# Sheet1.net
KiCad netlist of a schematic drawn in Altium Designer
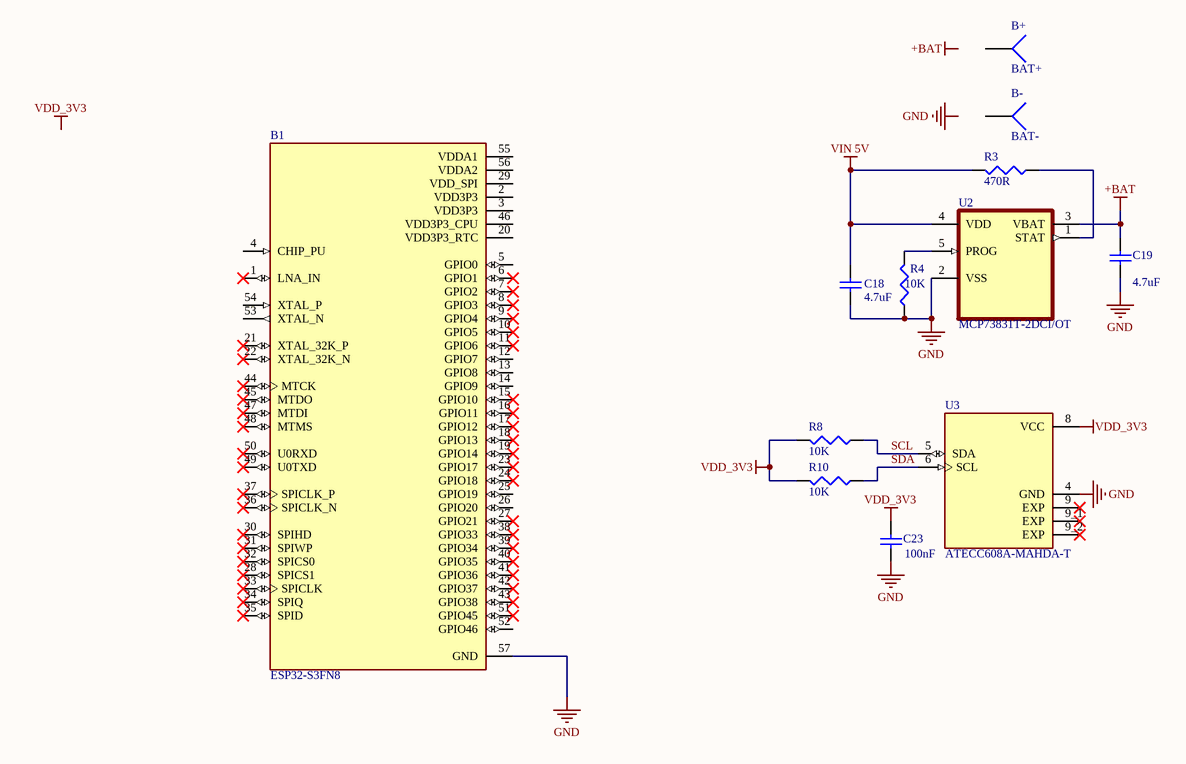
[diagram p0: Sheet1.SchDoc]

(export (version "E")
  (design (tool "Eeschema 10.0.6"))
  (components
    (comp (ref "B+")
      (value "BAT+")
      (footprint "PIN1")
      (description "Socket")
      (fields (field (name "PUBLISHER") "Altium Limited"))
      (libsource (lib "Miscellaneous Connectors") (part "Socket"))
    )
    (comp (ref "B-")
      (value "BAT-")
      (footprint "PIN1")
      (description "Socket")
      (fields (field (name "PUBLISHER") "Altium Limited"))
      (libsource (lib "Miscellaneous Connectors") (part "Socket"))
    )
    (comp (ref "B1")
      (value "ESP32-S3FN8")
      (footprint "ESP32-S3FN8:QFN40P700X700X90-57N")
      (fields (field (name "MF") "{'manufacturer': u'Espressif Systems'}"))
      (libsource (lib "*") (part "ESP32-S3FN8"))
    )
    (comp (ref "C18")
      (value "4.7uF")
      (footprint "C1206")
      (description "Capacitor (Semiconductor SIM Model)")
      (fields (field (name "Comment") "Cap Semi") (field (name "PUBLISHER") "Altium Limited"))
      (libsource (lib "Miscellaneous Devices") (part "Cap Semi"))
    )
    (comp (ref "C19")
      (value "4.7uF")
      (footprint "C1206")
      (description "Capacitor (Semiconductor SIM Model)")
      (fields (field (name "Comment") "Cap Semi") (field (name "PUBLISHER") "Altium Limited"))
      (libsource (lib "Miscellaneous Devices") (part "Cap Semi"))
    )
    (comp (ref "C23")
      (value "100nF")
      (footprint "C1206")
      (description "Capacitor (Semiconductor SIM Model)")
      (fields (field (name "Comment") "Cap Semi") (field (name "PUBLISHER") "Altium Limited"))
      (libsource (lib "Miscellaneous Devices") (part "Cap Semi"))
    )
    (comp (ref "R3")
      (value "470R")
      (footprint "J1-0603")
      (description "Resistor")
      (fields (field (name "Comment") "Res3") (field (name "PUBLISHER") "Altium Limited"))
      (libsource (lib "Miscellaneous Devices") (part "Res3"))
    )
    (comp (ref "R4")
      (value "10K")
      (footprint "J1-0603")
      (description "Resistor")
      (fields (field (name "Comment") "Res3") (field (name "PUBLISHER") "Altium Limited"))
      (libsource (lib "Miscellaneous Devices") (part "Res3"))
    )
    (comp (ref "R8")
      (value "10K")
      (footprint "J1-0603")
      (description "Resistor")
      (fields (field (name "Comment") "Res3") (field (name "PUBLISHER") "Altium Limited"))
      (libsource (lib "Miscellaneous Devices") (part "Res3"))
    )
    (comp (ref "R10")
      (value "10K")
      (footprint "J1-0603")
      (description "Resistor")
      (fields (field (name "Comment") "Res3") (field (name "PUBLISHER") "Altium Limited"))
      (libsource (lib "Miscellaneous Devices") (part "Res3"))
    )
    (comp (ref "U2")
      (value "MCP73831T-2DCI/OT")
      (footprint "MCP73831T-2DCI_OT:SOT95P270X145-5N")
      (description "Li-Polymer Charge Management Controllers, SOT23-5")
      (fields (field (name "MF") "{'manufacturer': u'Microchip'}") (field (name "MP") "MCP73831T-2DCI-OT"))
      (libsource (lib "*") (part "MCP73831T-2DCI/OT"))
    )
    (comp (ref "U3")
      (value "ATECC608A-MAHDA-T")
      (footprint "ATECC608A-MAHDA-T:SON50P200X300X60-9N")
      (description "IC AUTHENTICATION CHIP 8UDFN")
      (fields (field (name "MF") "{'manufacturer': u'Microchip Technology'}"))
      (libsource (lib "*") (part "ATECC608A-MAHDA-T"))
    )
  )
  (nets
    (net (code "1") (name "+BAT") (class "Default")
      (node (ref "C19") (pin "2") (pinfunction "2_2") (pintype "passive"))
      (node (ref "U2") (pin "3") (pinfunction "VBAT_3") (pintype "power_in"))
    )
    (net (code "2") (name "/SCL") (class "Default")
      (node (ref "R8") (pin "1") (pinfunction "1_1") (pintype "passive"))
      (node (ref "U3") (pin "5") (pinfunction "SDA_5") (pintype "bidirectional"))
    )
    (net (code "3") (name "/SDA") (class "Default")
      (node (ref "R10") (pin "1") (pinfunction "1_1") (pintype "passive"))
      (node (ref "U3") (pin "6") (pinfunction "SCL_6") (pintype "input"))
    )
    (net (code "4") (name "GND") (class "Default")
      (node (ref "B1") (pin "57") (pinfunction "GND_57") (pintype "power_in"))
      (node (ref "C18") (pin "1") (pinfunction "1_1") (pintype "passive"))
      (node (ref "C19") (pin "1") (pinfunction "1_1") (pintype "passive"))
      (node (ref "C23") (pin "1") (pinfunction "1_1") (pintype "passive"))
      (node (ref "R4") (pin "1") (pinfunction "1_1") (pintype "passive"))
      (node (ref "U2") (pin "2") (pinfunction "VSS_2") (pintype "power_in"))
      (node (ref "U3") (pin "4") (pinfunction "GND_4") (pintype "power_in"))
    )
    (net (code "5") (name "Net-(U2-PROG)") (class "Default")
      (node (ref "R4") (pin "2") (pinfunction "2_2") (pintype "passive"))
      (node (ref "U2") (pin "5") (pinfunction "PROG_5") (pintype "input"))
    )
    (net (code "6") (name "Net-(U2-STAT)") (class "Default")
      (node (ref "R3") (pin "1") (pinfunction "1_1") (pintype "passive"))
      (node (ref "U2") (pin "1") (pinfunction "STAT_1") (pintype "output"))
    )
    (net (code "7") (name "VDD_3V3") (class "Default")
      (node (ref "C23") (pin "2") (pinfunction "2_2") (pintype "passive"))
      (node (ref "R10") (pin "2") (pinfunction "2_2") (pintype "passive"))
      (node (ref "R8") (pin "2") (pinfunction "2_2") (pintype "passive"))
      (node (ref "U3") (pin "8") (pinfunction "VCC_8") (pintype "power_in"))
    )
    (net (code "8") (name "VIN 5V") (class "Default")
      (node (ref "C18") (pin "2") (pinfunction "2_2") (pintype "passive"))
      (node (ref "R3") (pin "2") (pinfunction "2_2") (pintype "passive"))
      (node (ref "U2") (pin "4") (pinfunction "VDD_4") (pintype "power_in"))
    )
    (net (code "9") (name "unconnected-(B+-Pad1)") (class "Default")
      (node (ref "B+") (pin "1") (pinfunction "1_1") (pintype "passive"))
    )
    (net (code "10") (name "unconnected-(B--Pad1)") (class "Default")
      (node (ref "B-") (pin "1") (pinfunction "1_1") (pintype "passive"))
    )
    (net (code "11") (name "unconnected-(B1-CHIP_PU-Pad4)") (class "Default")
      (node (ref "B1") (pin "4") (pinfunction "CHIP_PU_4") (pintype "input"))
    )
    (net (code "12") (name "unconnected-(B1-GPIO0-Pad5)") (class "Default")
      (node (ref "B1") (pin "5") (pinfunction "GPIO0_5") (pintype "bidirectional"))
    )
    (net (code "13") (name "unconnected-(B1-GPIO1-Pad6)") (class "Default")
      (node (ref "B1") (pin "6") (pinfunction "GPIO1_6") (pintype "bidirectional+no_connect"))
    )
    (net (code "14") (name "unconnected-(B1-GPIO2-Pad7)") (class "Default")
      (node (ref "B1") (pin "7") (pinfunction "GPIO2_7") (pintype "bidirectional+no_connect"))
    )
    (net (code "15") (name "unconnected-(B1-GPIO3-Pad8)") (class "Default")
      (node (ref "B1") (pin "8") (pinfunction "GPIO3_8") (pintype "bidirectional+no_connect"))
    )
    (net (code "16") (name "unconnected-(B1-GPIO4-Pad9)") (class "Default")
      (node (ref "B1") (pin "9") (pinfunction "GPIO4_9") (pintype "bidirectional+no_connect"))
    )
    (net (code "17") (name "unconnected-(B1-GPIO5-Pad10)") (class "Default")
      (node (ref "B1") (pin "10") (pinfunction "GPIO5_10") (pintype "bidirectional+no_connect"))
    )
    (net (code "18") (name "unconnected-(B1-GPIO6-Pad11)") (class "Default")
      (node (ref "B1") (pin "11") (pinfunction "GPIO6_11") (pintype "bidirectional+no_connect"))
    )
    (net (code "19") (name "unconnected-(B1-GPIO7-Pad12)") (class "Default")
      (node (ref "B1") (pin "12") (pinfunction "GPIO7_12") (pintype "bidirectional"))
    )
    (net (code "20") (name "unconnected-(B1-GPIO8-Pad13)") (class "Default")
      (node (ref "B1") (pin "13") (pinfunction "GPIO8_13") (pintype "bidirectional"))
    )
    (net (code "21") (name "unconnected-(B1-GPIO9-Pad14)") (class "Default")
      (node (ref "B1") (pin "14") (pinfunction "GPIO9_14") (pintype "bidirectional"))
    )
    (net (code "22") (name "unconnected-(B1-GPIO10-Pad15)") (class "Default")
      (node (ref "B1") (pin "15") (pinfunction "GPIO10_15") (pintype "bidirectional+no_connect"))
    )
    (net (code "23") (name "unconnected-(B1-GPIO11-Pad16)") (class "Default")
      (node (ref "B1") (pin "16") (pinfunction "GPIO11_16") (pintype "bidirectional+no_connect"))
    )
    (net (code "24") (name "unconnected-(B1-GPIO12-Pad17)") (class "Default")
      (node (ref "B1") (pin "17") (pinfunction "GPIO12_17") (pintype "bidirectional+no_connect"))
    )
    (net (code "25") (name "unconnected-(B1-GPIO13-Pad18)") (class "Default")
      (node (ref "B1") (pin "18") (pinfunction "GPIO13_18") (pintype "bidirectional+no_connect"))
    )
    (net (code "26") (name "unconnected-(B1-GPIO14-Pad19)") (class "Default")
      (node (ref "B1") (pin "19") (pinfunction "GPIO14_19") (pintype "bidirectional+no_connect"))
    )
    (net (code "27") (name "unconnected-(B1-GPIO17-Pad23)") (class "Default")
      (node (ref "B1") (pin "23") (pinfunction "GPIO17_23") (pintype "bidirectional+no_connect"))
    )
    (net (code "28") (name "unconnected-(B1-GPIO18-Pad24)") (class "Default")
      (node (ref "B1") (pin "24") (pinfunction "GPIO18_24") (pintype "bidirectional+no_connect"))
    )
    (net (code "29") (name "unconnected-(B1-GPIO19-Pad25)") (class "Default")
      (node (ref "B1") (pin "25") (pinfunction "GPIO19_25") (pintype "bidirectional"))
    )
    (net (code "30") (name "unconnected-(B1-GPIO20-Pad26)") (class "Default")
      (node (ref "B1") (pin "26") (pinfunction "GPIO20_26") (pintype "bidirectional"))
    )
    (net (code "31") (name "unconnected-(B1-GPIO21-Pad27)") (class "Default")
      (node (ref "B1") (pin "27") (pinfunction "GPIO21_27") (pintype "bidirectional+no_connect"))
    )
    (net (code "32") (name "unconnected-(B1-GPIO33-Pad38)") (class "Default")
      (node (ref "B1") (pin "38") (pinfunction "GPIO33_38") (pintype "bidirectional+no_connect"))
    )
    (net (code "33") (name "unconnected-(B1-GPIO34-Pad39)") (class "Default")
      (node (ref "B1") (pin "39") (pinfunction "GPIO34_39") (pintype "bidirectional+no_connect"))
    )
    (net (code "34") (name "unconnected-(B1-GPIO35-Pad40)") (class "Default")
      (node (ref "B1") (pin "40") (pinfunction "GPIO35_40") (pintype "bidirectional+no_connect"))
    )
    (net (code "35") (name "unconnected-(B1-GPIO36-Pad41)") (class "Default")
      (node (ref "B1") (pin "41") (pinfunction "GPIO36_41") (pintype "bidirectional+no_connect"))
    )
    (net (code "36") (name "unconnected-(B1-GPIO37-Pad42)") (class "Default")
      (node (ref "B1") (pin "42") (pinfunction "GPIO37_42") (pintype "bidirectional+no_connect"))
    )
    (net (code "37") (name "unconnected-(B1-GPIO38-Pad43)") (class "Default")
      (node (ref "B1") (pin "43") (pinfunction "GPIO38_43") (pintype "bidirectional+no_connect"))
    )
    (net (code "38") (name "unconnected-(B1-GPIO45-Pad51)") (class "Default")
      (node (ref "B1") (pin "51") (pinfunction "GPIO45_51") (pintype "bidirectional+no_connect"))
    )
    (net (code "39") (name "unconnected-(B1-GPIO46-Pad52)") (class "Default")
      (node (ref "B1") (pin "52") (pinfunction "GPIO46_52") (pintype "bidirectional"))
    )
    (net (code "40") (name "unconnected-(B1-LNA_IN-Pad1)") (class "Default")
      (node (ref "B1") (pin "1") (pinfunction "LNA_IN_1") (pintype "bidirectional+no_connect"))
    )
    (net (code "41") (name "unconnected-(B1-MTCK-Pad44)") (class "Default")
      (node (ref "B1") (pin "44") (pinfunction "MTCK_44") (pintype "bidirectional+no_connect"))
    )
    (net (code "42") (name "unconnected-(B1-MTDI-Pad47)") (class "Default")
      (node (ref "B1") (pin "47") (pinfunction "MTDI_47") (pintype "bidirectional+no_connect"))
    )
    (net (code "43") (name "unconnected-(B1-MTDO-Pad45)") (class "Default")
      (node (ref "B1") (pin "45") (pinfunction "MTDO_45") (pintype "bidirectional+no_connect"))
    )
    (net (code "44") (name "unconnected-(B1-MTMS-Pad48)") (class "Default")
      (node (ref "B1") (pin "48") (pinfunction "MTMS_48") (pintype "bidirectional+no_connect"))
    )
    (net (code "45") (name "unconnected-(B1-SPICLK-Pad33)") (class "Default")
      (node (ref "B1") (pin "33") (pinfunction "SPICLK_33") (pintype "bidirectional+no_connect"))
    )
    (net (code "46") (name "unconnected-(B1-SPICLK_N-Pad36)") (class "Default")
      (node (ref "B1") (pin "36") (pinfunction "SPICLK_N_36") (pintype "bidirectional+no_connect"))
    )
    (net (code "47") (name "unconnected-(B1-SPICLK_P-Pad37)") (class "Default")
      (node (ref "B1") (pin "37") (pinfunction "SPICLK_P_37") (pintype "bidirectional+no_connect"))
    )
    (net (code "48") (name "unconnected-(B1-SPICS0-Pad32)") (class "Default")
      (node (ref "B1") (pin "32") (pinfunction "SPICS0_32") (pintype "bidirectional+no_connect"))
    )
    (net (code "49") (name "unconnected-(B1-SPICS1-Pad28)") (class "Default")
      (node (ref "B1") (pin "28") (pinfunction "SPICS1_28") (pintype "bidirectional+no_connect"))
    )
    (net (code "50") (name "unconnected-(B1-SPID-Pad35)") (class "Default")
      (node (ref "B1") (pin "35") (pinfunction "SPID_35") (pintype "bidirectional+no_connect"))
    )
    (net (code "51") (name "unconnected-(B1-SPIHD-Pad30)") (class "Default")
      (node (ref "B1") (pin "30") (pinfunction "SPIHD_30") (pintype "bidirectional+no_connect"))
    )
    (net (code "52") (name "unconnected-(B1-SPIQ-Pad34)") (class "Default")
      (node (ref "B1") (pin "34") (pinfunction "SPIQ_34") (pintype "bidirectional+no_connect"))
    )
    (net (code "53") (name "unconnected-(B1-SPIWP-Pad31)") (class "Default")
      (node (ref "B1") (pin "31") (pinfunction "SPIWP_31") (pintype "bidirectional+no_connect"))
    )
    (net (code "54") (name "unconnected-(B1-U0RXD-Pad50)") (class "Default")
      (node (ref "B1") (pin "50") (pinfunction "U0RXD_50") (pintype "bidirectional+no_connect"))
    )
    (net (code "55") (name "unconnected-(B1-U0TXD-Pad49)") (class "Default")
      (node (ref "B1") (pin "49") (pinfunction "U0TXD_49") (pintype "bidirectional+no_connect"))
    )
    (net (code "56") (name "unconnected-(B1-VDD3P3-Pad2)") (class "Default")
      (node (ref "B1") (pin "2") (pinfunction "VDD3P3_2") (pintype "power_in"))
    )
    (net (code "57") (name "unconnected-(B1-VDD3P3-Pad3)") (class "Default")
      (node (ref "B1") (pin "3") (pinfunction "VDD3P3_3") (pintype "power_in"))
    )
    (net (code "58") (name "unconnected-(B1-VDD3P3_CPU-Pad46)") (class "Default")
      (node (ref "B1") (pin "46") (pinfunction "VDD3P3_CPU_46") (pintype "power_in"))
    )
    (net (code "59") (name "unconnected-(B1-VDD3P3_RTC-Pad20)") (class "Default")
      (node (ref "B1") (pin "20") (pinfunction "VDD3P3_RTC_20") (pintype "power_in"))
    )
    (net (code "60") (name "unconnected-(B1-VDDA1-Pad55)") (class "Default")
      (node (ref "B1") (pin "55") (pinfunction "VDDA1_55") (pintype "power_in"))
    )
    (net (code "61") (name "unconnected-(B1-VDDA2-Pad56)") (class "Default")
      (node (ref "B1") (pin "56") (pinfunction "VDDA2_56") (pintype "power_in"))
    )
    (net (code "62") (name "unconnected-(B1-VDD_SPI-Pad29)") (class "Default")
      (node (ref "B1") (pin "29") (pinfunction "VDD_SPI_29") (pintype "power_in"))
    )
    (net (code "63") (name "unconnected-(B1-XTAL_32K_N-Pad22)") (class "Default")
      (node (ref "B1") (pin "22") (pinfunction "XTAL_32K_N_22") (pintype "bidirectional+no_connect"))
    )
    (net (code "64") (name "unconnected-(B1-XTAL_32K_P-Pad21)") (class "Default")
      (node (ref "B1") (pin "21") (pinfunction "XTAL_32K_P_21") (pintype "bidirectional+no_connect"))
    )
    (net (code "65") (name "unconnected-(B1-XTAL_N-Pad53)") (class "Default")
      (node (ref "B1") (pin "53") (pinfunction "XTAL_N_53") (pintype "output"))
    )
    (net (code "66") (name "unconnected-(B1-XTAL_P-Pad54)") (class "Default")
      (node (ref "B1") (pin "54") (pinfunction "XTAL_P_54") (pintype "input"))
    )
    (net (code "67") (name "unconnected-(U3-EXP-Pad9)") (class "Default")
      (node (ref "U3") (pin "9") (pinfunction "EXP_9") (pintype "power_in+no_connect"))
    )
    (net (code "68") (name "unconnected-(U3-EXP-Pad9_1)") (class "Default")
      (node (ref "U3") (pin "9_1") (pinfunction "EXP_9_1") (pintype "power_in+no_connect"))
    )
    (net (code "69") (name "unconnected-(U3-EXP-Pad9_2)") (class "Default")
      (node (ref "U3") (pin "9_2") (pinfunction "EXP_9_2") (pintype "power_in+no_connect"))
    )
  )
)
